# WCS1500_PCB.net
KiCad netlist of a schematic drawn in EAGLE
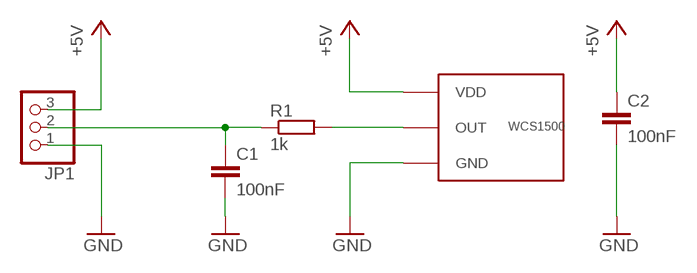
[diagram p0: schematic, sheet 1]

(export (version "E")
  (design (tool "Eeschema 10.0.6"))
  (components
    (comp (ref "C1")
      (value "100nF")
      (footprint "eagle-import:C0603")
      (libsource (lib "eagle-import") (part "C-EUC0603"))
    )
    (comp (ref "C2")
      (value "100nF")
      (footprint "eagle-import:C0603")
      (libsource (lib "eagle-import") (part "C-EUC0603"))
    )
    (comp (ref "JP1")
      (value "PINHD-1X3")
      (footprint "eagle-import:1X03")
      (libsource (lib "eagle-import") (part "PINHD-1X3"))
    )
    (comp (ref "R1")
      (value "1k")
      (footprint "eagle-import:R0603")
      (libsource (lib "eagle-import") (part "R-EU_R0603"))
    )
    (comp (ref "U$1")
      (value "WCS1500")
      (footprint "eagle-import:WCS1500")
      (libsource (lib "eagle-import") (part "WCS1500"))
    )
  )
  (nets
    (net (code "1") (name "+5V") (class "Default")
      (node (ref "C2") (pin "1") (pinfunction "1_1") (pintype "passive"))
      (node (ref "JP1") (pin "3") (pinfunction "3_3") (pintype "passive"))
      (node (ref "U$1") (pin "VDD") (pinfunction "VDD_VDD") (pintype "bidirectional"))
    )
    (net (code "2") (name "GND") (class "Default")
      (node (ref "C1") (pin "2") (pinfunction "2_2") (pintype "passive"))
      (node (ref "C2") (pin "2") (pinfunction "2_2") (pintype "passive"))
      (node (ref "JP1") (pin "1") (pinfunction "1_1") (pintype "passive"))
      (node (ref "U$1") (pin "GND") (pinfunction "GND_GND") (pintype "bidirectional"))
    )
    (net (code "3") (name "Net-(C1-Pad1)") (class "Default")
      (node (ref "C1") (pin "1") (pinfunction "1_1") (pintype "passive"))
      (node (ref "JP1") (pin "2") (pinfunction "2_2") (pintype "passive"))
      (node (ref "R1") (pin "1") (pinfunction "1_1") (pintype "passive"))
    )
    (net (code "4") (name "Net-(R1-Pad2)") (class "Default")
      (node (ref "R1") (pin "2") (pinfunction "2_2") (pintype "passive"))
      (node (ref "U$1") (pin "OUT") (pinfunction "OUT_OUT") (pintype "bidirectional"))
    )
  )
)
